# Power_Supplies.net
KiCad netlist of a schematic drawn in Altium Designer
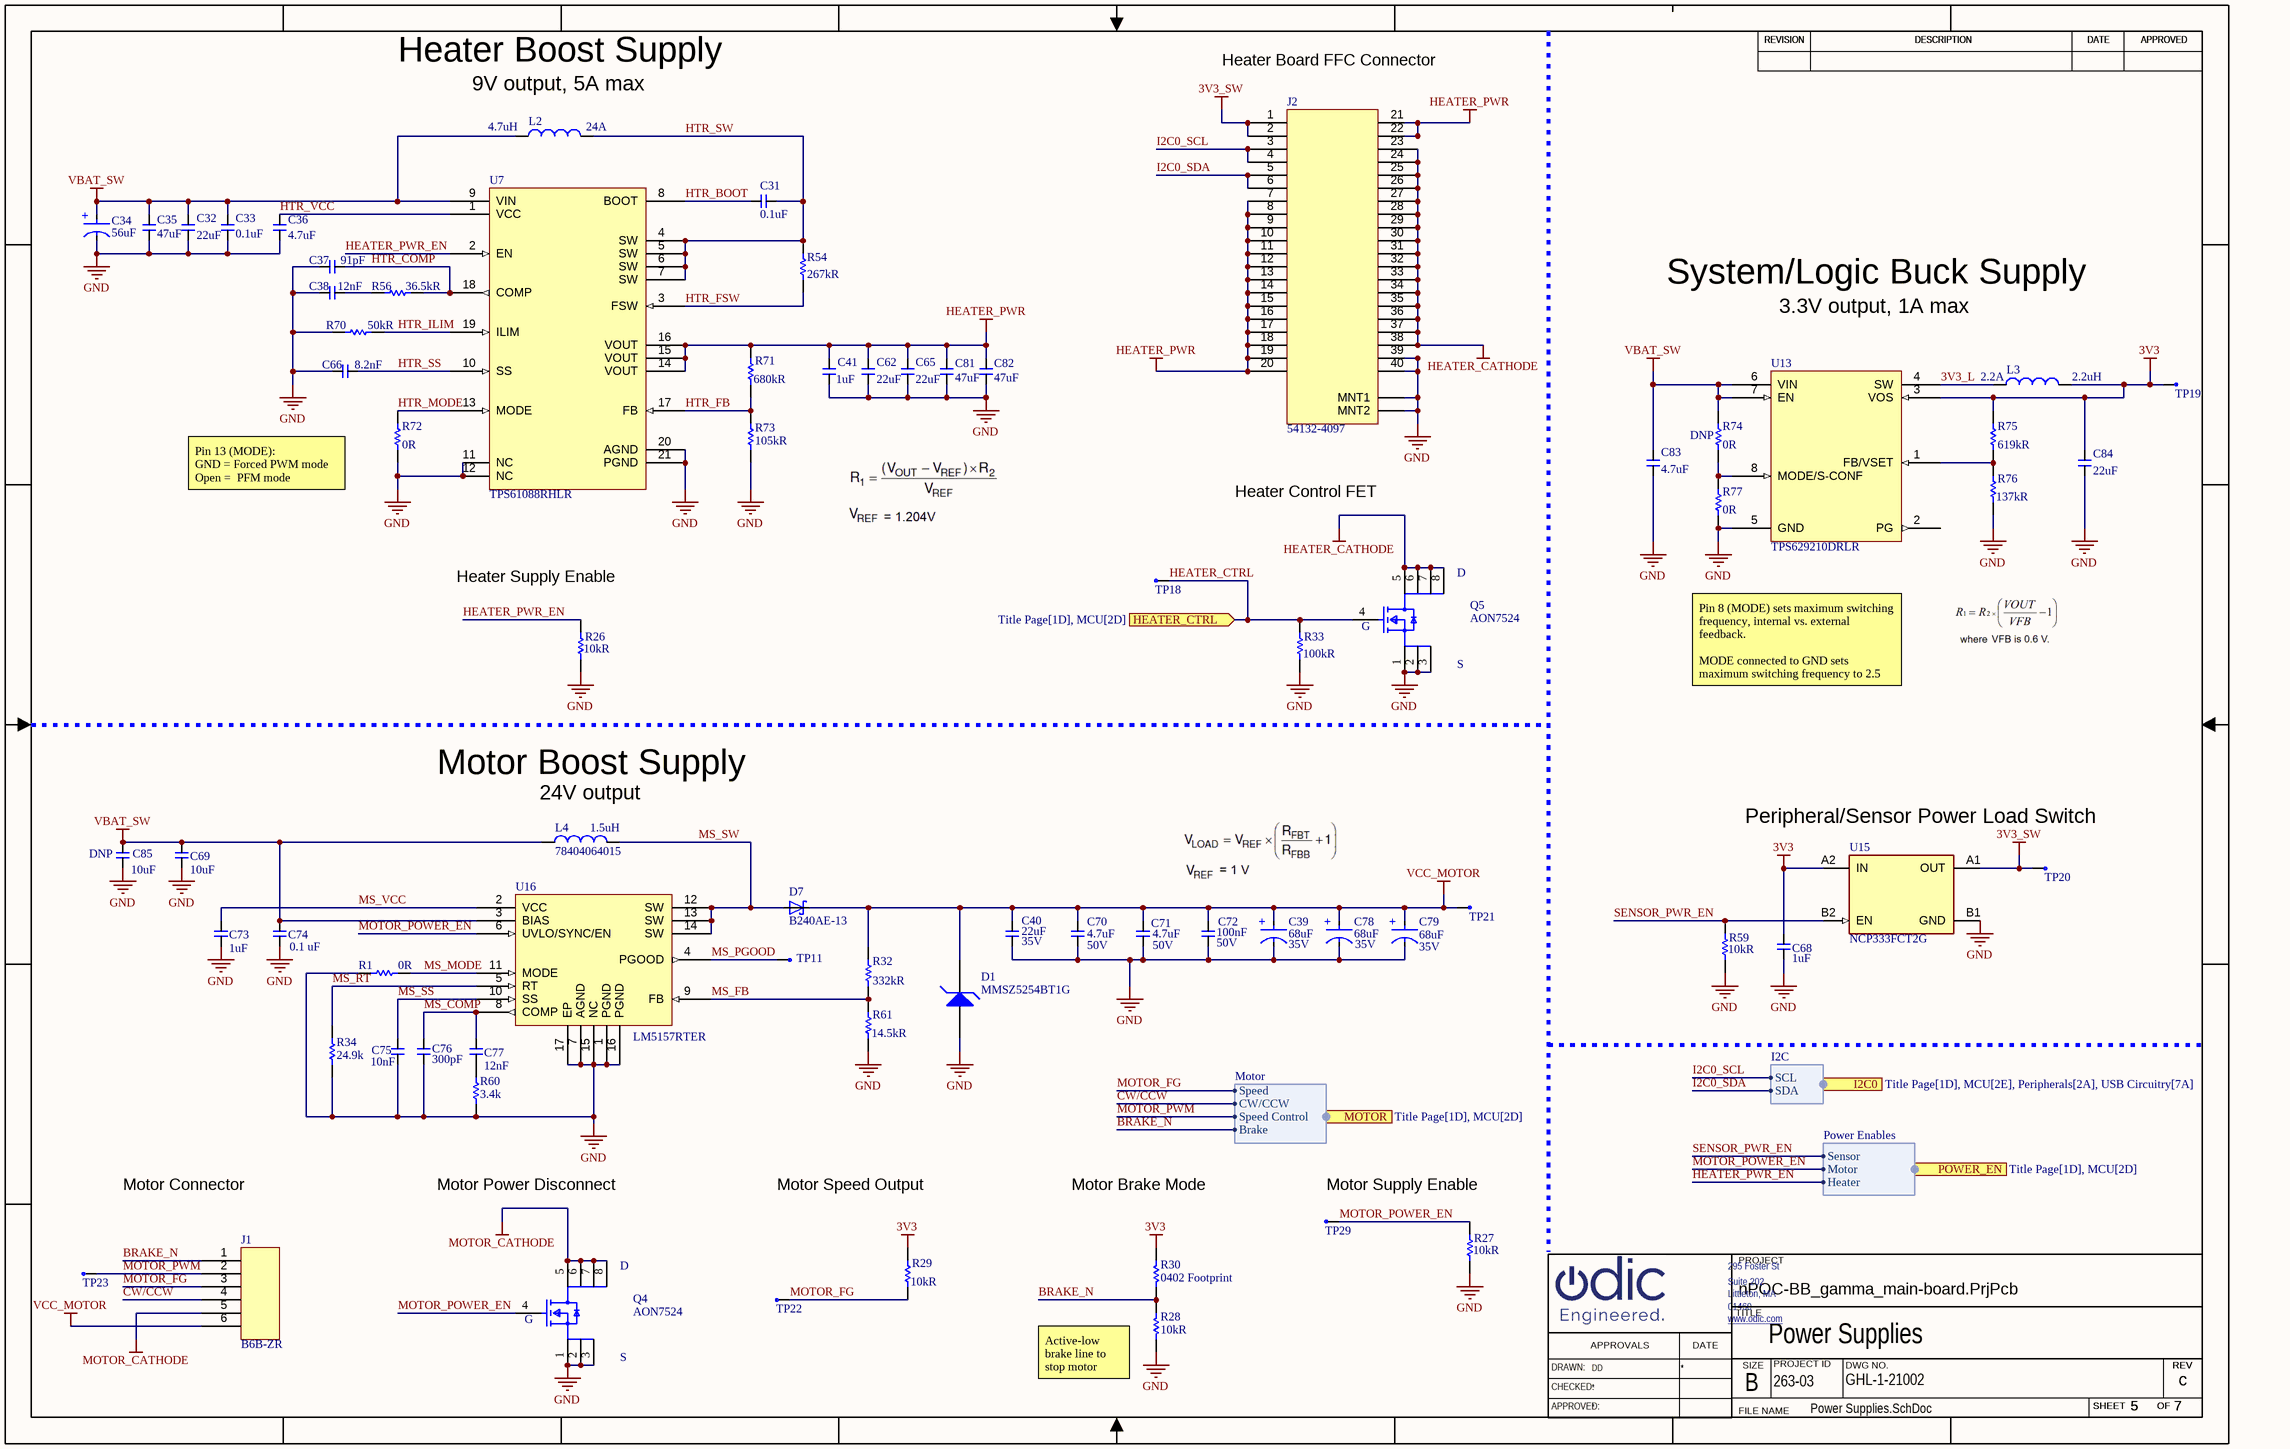
[diagram p0: Power Supplies.SchDoc]

(export (version "E")
  (design (tool "Eeschema 10.0.6"))
  (components
    (comp (ref "C31")
      (value "0.1uF")
      (footprint "C0402")
      (description "Ceramic capacitor SMD 0402 100nF 16V X7R 10%")
      (fields (field (name "VOLTAGE") "16V") (field (name "TOLERANCE") "10%"))
      (libsource (lib "Odic Inc") (part "cAP"))
    )
    (comp (ref "C32")
      (value "22uF")
      (footprint "C1206")
      (description "1206 22 uF 16 V ±10% Tolerance X5R SMT Multilayer Ceramic Capacitor")
      (fields (field (name "VOLTAGE") "16V") (field (name "TOLERANCE") "10%"))
      (libsource (lib "Odic Inc") (part "cAP"))
    )
    (comp (ref "C33")
      (value "0.1uF")
      (footprint "C0402")
      (description "Ceramic capacitor SMD 0402 100nF 16V X7R 10%")
      (fields (field (name "VOLTAGE") "16V") (field (name "TOLERANCE") "10%"))
      (libsource (lib "Odic Inc") (part "cAP"))
    )
    (comp (ref "C34")
      (value "56uF")
      (footprint "cap_panasonic_svpf_code-b6")
      (description "Cap Aluminum Polymer 56uF 20VDC 20%( 5 X 5.9mm) SMD 0.03 Ohm 2800mA 5000h 105C T/R")
      (fields (field (name "VOLTAGE") "20V") (field (name "TOLERANCE") "20%"))
      (libsource (lib "Odic Inc") (part "polcap"))
    )
    (comp (ref "C35")
      (value "47uF")
      (footprint "C1210")
      (description "Multilayer Ceramic Capacitor, 47 uF, 16 V, 10%, X5R, 1210 [3225 Metric]")
      (fields (field (name "TOLERANCE") "10%") (field (name "Comment") "C1210_47u_16V_10pct"))
      (libsource (lib "Odic Inc") (part "cAP"))
    )
    (comp (ref "C36")
      (value "4.7uF")
      (footprint "C0402")
      (description "Cap Ceramic 4.7uF 10V X5R 20% SMD 0402 85°C Paper T/R")
      (fields (field (name "TOLERANCE") "20%"))
      (libsource (lib "Odic Inc") (part "cAP"))
    )
    (comp (ref "C37")
      (value "91pF")
      (footprint "C0402")
      (description "Multilayer Ceramic Capacitors MLCC - SMD/SMT 50V 91pF C0G 0402 5%")
      (fields (field (name "TOLERANCE") "5%") (field (name "Comment") "C0402_91p_50V_5pct"))
      (libsource (lib "Odic Inc") (part "cAP"))
    )
    (comp (ref "C38")
      (value "12nF")
      (footprint "C0402")
      (description "0402 12 nF 16 V ±10% Tolerance X7R SMT Multilayer Ceramic Capacitor")
      (fields (field (name "VOLTAGE") "16V") (field (name "TOLERANCE") "10%"))
      (libsource (lib "Odic Inc") (part "cAP"))
    )
    (comp (ref "C39")
      (value "68uF")
      (footprint "C7361-38")
      (description "Cap Tant Solid 68uF 35V V CASE 20% (7.3 X 6.1 X 3.45mm) SMD 7361-38 0.5 Ohm 125AHA T/R")
      (fields
        (field (name "VOLTAGE RATING") "35V")
        (field (name "TOLERANCE") "20%")
        (field (name "Comment") "TAJV686M035RNJ")
      )
      (libsource (lib "Odic Inc") (part "polcap"))
    )
    (comp (ref "C40")
      (value "22uF")
      (footprint "c0805")
      (description "Multilayer Ceramic Capacitor, 22 uF, 35 V, ± 20%, X5R, 0805 [2012 Metric]")
      (fields
        (field (name "VOLTAGE RATING") "35V")
        (field (name "TOLERANCE") "20%")
        (field (name "Comment") "C0805_22u_35V_20pct")
      )
      (libsource (lib "Odic Inc") (part "cAP"))
    )
    (comp (ref "C41")
      (value "C0603_1u_25V_10pct")
      (footprint "C0603")
      (description "Multilayer Ceramic Capacitors (High dielectric type), 25V, 1 uF, ± 10 %, 0603, X5R/B, RoHS")
      (fields
        (field (name "CAPACITANCE") "1uF")
        (field (name "TOLERANCE") "10%")
        (field (name "VOLTAGE") "25V")
      )
      (libsource (lib "Odic Inc") (part "cAP"))
    )
    (comp (ref "C62")
      (value "22uF")
      (footprint "C1206")
      (description "1206 22 uF 16 V ±10% Tolerance X5R SMT Multilayer Ceramic Capacitor")
      (fields (field (name "VOLTAGE") "16V") (field (name "TOLERANCE") "10%"))
      (libsource (lib "Odic Inc") (part "cAP"))
    )
    (comp (ref "C65")
      (value "22uF")
      (footprint "C1206")
      (description "1206 22 uF 16 V ±10% Tolerance X5R SMT Multilayer Ceramic Capacitor")
      (fields (field (name "VOLTAGE") "16V") (field (name "TOLERANCE") "10%"))
      (libsource (lib "Odic Inc") (part "cAP"))
    )
    (comp (ref "C66")
      (value "8.2nF")
      (footprint "C0402")
      (description "0402 8.2 nF 16 V ±10% Tolerance X7R SMT Multilayer Ceramic Capacitor")
      (fields (field (name "TOLERANCE") "10%") (field (name "Comment") "C0402_8n2_16V_10pct"))
      (libsource (lib "Odic Inc") (part "cAP"))
    )
    (comp (ref "C68")
      (value "C0402_1u_6V3_10pct")
      (footprint "C0402")
      (description "Cap Ceramic 1uF 6.3V X5R 10% SMD 0402 85C Paper T/R")
      (fields (field (name "CAPACITANCE") "1uF") (field (name "TOLERANCE") "10%"))
      (libsource (lib "Odic Inc") (part "cAP"))
    )
    (comp (ref "C69")
      (value "10uF")
      (footprint "C0603")
      (description "Cap Ceramic 10uF 35V X5R 20% Pad SMD 0603 85C T/R")
      (fields (field (name "TOLERANCE") "20%"))
      (libsource (lib "Odic Inc") (part "cAP"))
    )
    (comp (ref "C70")
      (value "4.7uF")
      (footprint "c0805")
      (description "Multilayer Ceramic Capacitor, 4.7 uF, 50 V, ± 10%, X5R, 0805 [2012 Metric]")
      (fields
        (field (name "VOLTAGE RATING") "50V")
        (field (name "TOLERANCE") "10%")
        (field (name "Comment") "C0805_4u7_50V_10pct")
      )
      (libsource (lib "Odic Inc") (part "cAP"))
    )
    (comp (ref "C71")
      (value "4.7uF")
      (footprint "c0805")
      (description "Multilayer Ceramic Capacitor, 4.7 uF, 50 V, ± 10%, X5R, 0805 [2012 Metric]")
      (fields
        (field (name "VOLTAGE RATING") "50V")
        (field (name "TOLERANCE") "10%")
        (field (name "Comment") "C0805_4u7_50V_10pct")
      )
      (libsource (lib "Odic Inc") (part "cAP"))
    )
    (comp (ref "C72")
      (value "100nF")
      (footprint "C0603")
      (description "CAP CER 0.1UF 50V X7R 0603")
      (fields (field (name "VOLTAGE RATING") "50V") (field (name "TOLERANCE") "10%"))
      (libsource (lib "Odic Inc") (part "cAP"))
    )
    (comp (ref "C73")
      (value "1uF")
      (footprint "C0603")
      (description "CAP CER 1UF 16V X5R 0603")
      (fields (field (name "TOLERANCE") "10%") (field (name "VOLTAGE") "16V"))
      (libsource (lib "Odic Inc") (part "cAP"))
    )
    (comp (ref "C74")
      (value "C0805_0u1_25V_10pct")
      (footprint "c0805")
      (description "Cap Cer 0.1UF 25V X7R 0805")
      (fields (field (name "CAPACITANCE") "0.1 uF") (field (name "TOLERANCE") "10%"))
      (libsource (lib "Odic Inc") (part "cAP"))
    )
    (comp (ref "C75")
      (value "10nF")
      (footprint "C0402")
      (description "Multilayer Ceramic Capacitor, 0.01 uF, 35 V, ± 10%, X7R, 0402 [1005 Metric]")
      (fields (field (name "TOLERANCE") "10%") (field (name "Comment") "C0402_10n_35V_10pct"))
      (libsource (lib "Odic Inc") (part "cAP"))
    )
    (comp (ref "C76")
      (value "300pF")
      (footprint "C0402")
      (description "Cap Ceramic 300pF 50V C0G 5% SMD 0402 125°C Paper T/R")
      (fields (field (name "TOLERANCE") "5%") (field (name "Comment") "C0402_300p_50V_5pct"))
      (libsource (lib "Odic Inc") (part "cAP"))
    )
    (comp (ref "C77")
      (value "12nF")
      (footprint "C0402")
      (description "0402 12 nF 16 V ±10% Tolerance X7R SMT Multilayer Ceramic Capacitor")
      (fields (field (name "VOLTAGE") "16V") (field (name "TOLERANCE") "10%"))
      (libsource (lib "Odic Inc") (part "cAP"))
    )
    (comp (ref "C78")
      (value "68uF")
      (footprint "C7361-38")
      (description "Cap Tant Solid 68uF 35V V CASE 20% (7.3 X 6.1 X 3.45mm) SMD 7361-38 0.5 Ohm 125AHA T/R")
      (fields
        (field (name "VOLTAGE RATING") "35V")
        (field (name "TOLERANCE") "20%")
        (field (name "Comment") "TAJV686M035RNJ")
      )
      (libsource (lib "Odic Inc") (part "polcap"))
    )
    (comp (ref "C79")
      (value "68uF")
      (footprint "C7361-38")
      (description "Cap Tant Solid 68uF 35V V CASE 20% (7.3 X 6.1 X 3.45mm) SMD 7361-38 0.5 Ohm 125AHA T/R")
      (fields
        (field (name "VOLTAGE RATING") "35V")
        (field (name "TOLERANCE") "20%")
        (field (name "Comment") "TAJV686M035RNJ")
      )
      (libsource (lib "Odic Inc") (part "polcap"))
    )
    (comp (ref "C81")
      (value "47uF")
      (footprint "C1210")
      (description "Multilayer Ceramic Capacitor, 47 uF, 16 V, 10%, X5R, 1210 [3225 Metric]")
      (fields (field (name "TOLERANCE") "10%") (field (name "Comment") "C1210_47u_16V_10pct"))
      (libsource (lib "Odic Inc") (part "cAP"))
    )
    (comp (ref "C82")
      (value "47uF")
      (footprint "C1210")
      (description "Multilayer Ceramic Capacitor, 47 uF, 16 V, 10%, X5R, 1210 [3225 Metric]")
      (fields (field (name "TOLERANCE") "10%") (field (name "Comment") "C1210_47u_16V_10pct"))
      (libsource (lib "Odic Inc") (part "cAP"))
    )
    (comp (ref "C83")
      (value "4.7uF")
      (footprint "c0805")
      (description "Multilayer Ceramic Capacitor, 4.7 uF, 16 V, ± 10%, X5R, 0805 [2012 Metric]")
      (fields (field (name "VOLTAGE") "16V") (field (name "TOLERANCE") "10%"))
      (libsource (lib "Odic Inc") (part "cAP"))
    )
    (comp (ref "C84")
      (value "C0603_22u_6V3_20pct")
      (footprint "C0603")
      (description "CAP CER 22UF 6.3V X5R 0603")
      (fields
        (field (name "CAPACITANCE") "22uF")
        (field (name "TOLERANCE") "20%")
        (field (name "VOLTAGE") "6.3V")
      )
      (libsource (lib "Odic Inc") (part "cAP"))
    )
    (comp (ref "C85")
      (value "10uF")
      (footprint "C0603")
      (description "Cap Ceramic 10uF 35V X5R 20% Pad SMD 0603 85C T/R")
      (fields (field (name "INSTALL") "DNP") (field (name "TOLERANCE") "20%"))
      (libsource (lib "Odic Inc") (part "cAP"))
    )
    (comp (ref "D1")
      (value "MMSZ5254BT1G")
      (footprint "sod123")
      (description "MMSZ5254BT1G Zener Diode, 27V 5% 500 mW SMT 2-Pin SOD-123")
      (fields (field (name "TOLERANCE") "5%"))
      (libsource (lib "Odic Inc") (part "Zener Symbol"))
    )
    (comp (ref "D7")
      (value "B240AE-13")
      (footprint "sma")
      (description "Diode Schottky 40V 2A 2-Pin DO-214AC T/R")
      (libsource (lib "Odic Inc") (part "B240AE-13"))
    )
    (comp (ref "J1")
      (value "B6B-ZR")
      (footprint "jst-b6b-zr")
      (description "Header B6B-ZR, 1.50mm, 6-contacts, top entry, THT, /2000/box")
      (libsource (lib "Odic Inc") (part "B6B-ZR-Symbol-1"))
    )
    (comp (ref "J2")
      (value "54132-4097")
      (footprint "molex_54132-4097")
      (description ".50MM Ffc/fpc Connectors 40CKT R/a SMT Zif Botton Contact")
      (libsource (lib "Odic Inc") (part "54132-4097-Symbol-1"))
    )
    (comp (ref "L2")
      (value "4.7uH")
      (footprint "ind2_vishay_ihlp5050ce")
      (description "Inductor Power Shielded Wirewound 4.7uH 20% 100KHz Powdered Iron 10A 15mOhm DCR 5050 T/R")
      (fields
        (field (name "SATURATION CURRENT") "24A")
        (field (name "TOLERANCE") "20%")
        (field (name "Comment") "IHLP5050CEER4R7M01")
      )
      (libsource (lib "Odic Inc") (part "IND"))
    )
    (comp (ref "L3")
      (value "DFE252012PD-2R2M=P2")
      (footprint "ind2_2520")
      (description "Ind Power Chip Shielded Wirewound 2.2uH 20% 1MHz Metal 2.2A 1008 Emboss T/R")
      (fields
        (field (name "INDUCTANCE") "2.2uH")
        (field (name "CURRENT RATING") "2.2A")
        (field (name "TOLERANCE") "+/-20%")
      )
      (libsource (lib "Odic Inc") (part "IND"))
    )
    (comp (ref "L4")
      (value "78404064015")
      (footprint "ind2_wurth_78404064015")
      (description "WE-LQSA SMT Semi-Shielded Power Inductor 1.5uH 6.1 A 13mOhm Max")
      (fields (field (name "ALTIUM_VALUE") "1.5uH"))
      (libsource (lib "Odic Inc") (part "IND"))
    )
    (comp (ref "Q4")
      (value "AON7524")
      (footprint "dfn8_3x3_p65mm_fet")
      (description "Trans Mosfet N-ch 30V 28A 8-PIN Dfn-a Ep")
      (libsource (lib "Odic Inc") (part "e0baf4780622716b99a4fe4ad34e686"))
    )
    (comp (ref "Q5")
      (value "AON7524")
      (footprint "dfn8_3x3_p65mm_fet")
      (description "Trans Mosfet N-ch 30V 28A 8-PIN Dfn-a Ep")
      (libsource (lib "Odic Inc") (part "e0baf4780622716b99a4fe4ad34e686"))
    )
    (comp (ref "R1")
      (value "0R")
      (footprint "R0402")
      (description "RES 0 OHM JUMPER 1/16W 0402")
      (libsource (lib "Odic Inc") (part "RES"))
    )
    (comp (ref "R26")
      (value "R0402_10k_1pct")
      (footprint "R0402")
      (description "Res Thick Film 0402 10K Ohm 1% 1/16W ±100ppm/°C Molded SMD SMD T/R")
      (fields (field (name "RESISTANCE") "10kR") (field (name "TOLERANCE") "1%"))
      (libsource (lib "Odic Inc") (part "RES"))
    )
    (comp (ref "R27")
      (value "R0402_10k_1pct")
      (footprint "R0402")
      (description "Res Thick Film 0402 10K Ohm 1% 1/16W ±100ppm/°C Molded SMD SMD T/R")
      (fields (field (name "RESISTANCE") "10kR") (field (name "TOLERANCE") "1%"))
      (libsource (lib "Odic Inc") (part "RES"))
    )
    (comp (ref "R28")
      (value "R0402_10k_1pct")
      (footprint "R0402")
      (description "Res Thick Film 0402 10K Ohm 1% 1/16W ±100ppm/°C Molded SMD SMD T/R")
      (fields (field (name "RESISTANCE") "10kR") (field (name "TOLERANCE") "1%"))
      (libsource (lib "Odic Inc") (part "RES"))
    )
    (comp (ref "R29")
      (value "R0402_10k_1pct")
      (footprint "R0402")
      (description "Res Thick Film 0402 10K Ohm 1% 1/16W ±100ppm/°C Molded SMD SMD T/R")
      (fields (field (name "RESISTANCE") "10kR") (field (name "TOLERANCE") "1%"))
      (libsource (lib "Odic Inc") (part "RES"))
    )
    (comp (ref "R30")
      (value "0402 Footprint")
      (footprint "R0402")
      (description "Unpopulated 0402 pads. No part number associated with this \"component\"")
      (libsource (lib "Odic Inc") (part "RES"))
    )
    (comp (ref "R32")
      (value "332kR")
      (footprint "R0402")
      (description "Res Thick Film 0402 332K Ohm 1% 0.1W(1/10W) ±100ppm/°C Pad SMD Automotive T/R")
      (fields (field (name "TOLERANCE") "1%") (field (name "Comment") "R0402_332k_1pct"))
      (libsource (lib "Odic Inc") (part "RES"))
    )
    (comp (ref "R33")
      (value "R0402_100k_1pct")
      (footprint "R0402")
      (description "Res General Purpose Thick Film 0402 100K Ohm 1% 1/16W ±100ppm/°C Molded SMD Paper T/R")
      (fields (field (name "RESISTANCE") "100kR") (field (name "TOLERANCE") "1%"))
      (libsource (lib "Odic Inc") (part "RES"))
    )
    (comp (ref "R34")
      (value "24.9k")
      (footprint "R0402")
      (description "Res Thick Film 0402 24.9K Ohm 1% 1/10W ±100ppm/¦C SMD Punched Carrier T/R")
      (fields (field (name "TOLERANCE") "1%"))
      (libsource (lib "Odic Inc") (part "RES"))
    )
    (comp (ref "R54")
      (value "267kR")
      (footprint "R0402")
      (description "Res Thick Film 0402 267K Ohm 1% 0.063W ±100ppm/°C Molded SMD Paper T/R")
      (fields (field (name "TOLERANCE") "1%") (field (name "Comment") "R0402_267k_1pct"))
      (libsource (lib "Odic Inc") (part "RES"))
    )
    (comp (ref "R56")
      (value "36.5kR")
      (footprint "R0402")
      (description "SMD Chip Resistor, 36.5 kOhm, ï¿½ 1%, 63 mW, 0402 [1005 Metric], Thick Film, General Purpose")
      (fields (field (name "TOLERANCE") "1%") (field (name "Comment") "R0402_36k5_1pct"))
      (libsource (lib "Odic Inc") (part "RES"))
    )
    (comp (ref "R59")
      (value "R0402_10k_1pct")
      (footprint "R0402")
      (description "Res Thick Film 0402 10K Ohm 1% 1/16W ±100ppm/°C Molded SMD SMD T/R")
      (fields (field (name "RESISTANCE") "10kR") (field (name "TOLERANCE") "1%"))
      (libsource (lib "Odic Inc") (part "RES"))
    )
    (comp (ref "R60")
      (value "3.4k")
      (footprint "R0402")
      (description "SMD Chip Resistor, 3.4 kOhm, ± 1%, 100 mW, 0402 [1005 Metric], Thick Film, Precision")
      (fields (field (name "TOLERANCE") "1%"))
      (libsource (lib "Odic Inc") (part "RES"))
    )
    (comp (ref "R61")
      (value "14.5kR")
      (footprint "R0402")
      (description "RN73H 0402 (1005Metric) Chip Resistor ±1% ±25ppm/C 14.5kOhm 0.063W 1/16W")
      (fields (field (name "TOLERANCE") "1%") (field (name "Comment") "R0402_14k5_1pct"))
      (libsource (lib "Odic Inc") (part "RES"))
    )
    (comp (ref "R70")
      (value "50kR")
      (footprint "R0402")
      (fields (field (name "TOLERANCE") "1%") (field (name "Comment") "R0402_50k_1pct"))
      (libsource (lib "Odic Inc") (part "RES"))
    )
    (comp (ref "R71")
      (value "680kR")
      (footprint "R0402")
      (description "Res Thick Film 0402 680K Ohm 1% 1/16W ±100ppm/°C Molded SMD SMD Paper T/R")
      (fields (field (name "TOLERANCE") "1%") (field (name "Comment") "R0402_680k_1pct"))
      (libsource (lib "Odic Inc") (part "RES"))
    )
    (comp (ref "R72")
      (value "R0402_0R")
      (footprint "R0402")
      (description "RES 0 OHM JUMPER 1/16W 0402")
      (fields (field (name "RESISTANCE") "0R"))
      (libsource (lib "Odic Inc") (part "RES"))
    )
    (comp (ref "R73")
      (value "105kR")
      (footprint "R0402")
      (description "SMD Chip Resistor, 105 kOhm, ± 1%, 63 mW, 0402 [1005 Metric], Thick Film, General Purpose")
      (fields (field (name "TOLERANCE") "1%") (field (name "Comment") "R0402_105k_1pct"))
      (libsource (lib "Odic Inc") (part "RES"))
    )
    (comp (ref "R74")
      (value "R0402_0R")
      (footprint "R0402")
      (description "RES 0 OHM JUMPER 1/16W 0402")
      (fields (field (name "INSTALL") "DNP") (field (name "RESISTANCE") "0R"))
      (libsource (lib "Odic Inc") (part "RES"))
    )
    (comp (ref "R75")
      (value "619kR")
      (footprint "R0402")
      (description "RC FIXED RESISTOR 0402 (1005Metric) Chip Resistor ±1% ±100ppm/C 619kOhm 0.063W 1/16W")
      (fields (field (name "TOLERANCE") "1%") (field (name "Comment") "R0402_619k_1pct"))
      (libsource (lib "Odic Inc") (part "RES"))
    )
    (comp (ref "R76")
      (value "137kR")
      (footprint "R0402")
      (description "SMD Chip Resistor, 137 kOhm, ± 1%, 63 mW, 0402 [1005 Metric], Thick Film, General Purpose")
      (fields (field (name "TOLERANCE") "1%") (field (name "Comment") "R0402_137k_1pct"))
      (libsource (lib "Odic Inc") (part "RES"))
    )
    (comp (ref "R77")
      (value "R0402_0R")
      (footprint "R0402")
      (description "RES 0 OHM JUMPER 1/16W 0402")
      (fields (field (name "RESISTANCE") "0R"))
      (libsource (lib "Odic Inc") (part "RES"))
    )
    (comp (ref "TP11")
      (value "TPC30")
      (footprint "tpc30")
      (description "Test Point Circle 30")
      (libsource (lib "Odic Inc") (part "TPC"))
    )
    (comp (ref "TP18")
      (value "TPC30")
      (footprint "tpc30")
      (description "Test Point Circle 30")
      (libsource (lib "Odic Inc") (part "TPC"))
    )
    (comp (ref "TP19")
      (value "TPC30")
      (footprint "tpc30")
      (description "Test Point Circle 30")
      (libsource (lib "Odic Inc") (part "TPC"))
    )
    (comp (ref "TP20")
      (value "TPC30")
      (footprint "tpc30")
      (description "Test Point Circle 30")
      (libsource (lib "Odic Inc") (part "TPC"))
    )
    (comp (ref "TP21")
      (value "TPC30")
      (footprint "tpc30")
      (description "Test Point Circle 30")
      (libsource (lib "Odic Inc") (part "TPC"))
    )
    (comp (ref "TP22")
      (value "TPC30")
      (footprint "tpc30")
      (description "Test Point Circle 30")
      (libsource (lib "Odic Inc") (part "TPC"))
    )
    (comp (ref "TP23")
      (value "TPC30")
      (footprint "tpc30")
      (description "Test Point Circle 30")
      (libsource (lib "Odic Inc") (part "TPC"))
    )
    (comp (ref "TP29")
      (value "TPC30")
      (footprint "tpc30")
      (description "Test Point Circle 30")
      (libsource (lib "Odic Inc") (part "TPC"))
    )
    (comp (ref "U7")
      (value "TPS61088RHLR")
      (footprint "qfn20_3p5x4p5_p5mm")
      (description "IC REG BOOST ADJ 10A SYNC 20VQFN")
      (libsource (lib "Odic Inc") (part "TPS61088RHLR-Symbol-1"))
    )
    (comp (ref "U13")
      (value "TPS629210DRLR")
      (footprint "SOT-583")
      (libsource (lib "Odic Inc") (part "TPS629210DRLR-Symbol-1"))
    )
    (comp (ref "U15")
      (value "NCP333FCT2G")
      (footprint "bga4_p743xp743_p4mm")
      (description "IC LOAD SWITCH W/DIS 1.5A 4WLCSP")
      (libsource (lib "Odic Inc") (part "97019fd276bc7644be76e1f711e9589"))
    )
    (comp (ref "U16")
      (value "LM5157RTER")
      (footprint "qfn16_3x3_p5mm_thpad")
      (libsource (lib "Odic Inc") (part "LM5157RTER-Symbol-1"))
    )
  )
  (nets
    (net (code "5") (name "/3V3_L") (class "Default")
      (node (ref "L3") (pin "1") (pinfunction "1_1") (pintype "passive"))
      (node (ref "U13") (pin "4") (pinfunction "SW_4") (pintype "passive"))
    )
    (net (code "6") (name "/BRAKE_N") (class "Default")
      (node (ref "J1") (pin "1") (pinfunction "1_1") (pintype "passive"))
      (node (ref "R28") (pin "1") (pinfunction "1_1") (pintype "passive"))
      (node (ref "R30") (pin "2") (pinfunction "2_2") (pintype "passive"))
    )
    (net (code "7") (name "/CW{slash}CCW") (class "Default")
      (node (ref "J1") (pin "4") (pinfunction "4_4") (pintype "passive"))
    )
    (net (code "8") (name "/HEATER_CTRL") (class "Default")
      (node (ref "Q5") (pin "4") (pinfunction "G_4") (pintype "passive"))
      (node (ref "R33") (pin "2") (pinfunction "2_2") (pintype "passive"))
      (node (ref "TP18") (pin "1") (pinfunction "1_1") (pintype "passive"))
    )
    (net (code "9") (name "/HEATER_PWR_EN") (class "Default")
      (node (ref "R26") (pin "1") (pinfunction "1_1") (pintype "passive"))
      (node (ref "U7") (pin "2") (pinfunction "EN_2") (pintype "input"))
    )
    (net (code "10") (name "/HTR_BOOT") (class "Default")
      (node (ref "C31") (pin "2") (pinfunction "2_2") (pintype "passive"))
      (node (ref "U7") (pin "8") (pinfunction "BOOT_8") (pintype "passive"))
    )
    (net (code "11") (name "/HTR_COMP") (class "Default")
      (node (ref "C37") (pin "2") (pinfunction "2_2") (pintype "passive"))
      (node (ref "R56") (pin "2") (pinfunction "2_2") (pintype "passive"))
      (node (ref "U7") (pin "18") (pinfunction "COMP_18") (pintype "output"))
    )
    (net (code "12") (name "/HTR_FB") (class "Default")
      (node (ref "R71") (pin "1") (pinfunction "1_1") (pintype "passive"))
      (node (ref "R73") (pin "2") (pinfunction "2_2") (pintype "passive"))
      (node (ref "U7") (pin "17") (pinfunction "FB_17") (pintype "input"))
    )
    (net (code "13") (name "/HTR_FSW") (class "Default")
      (node (ref "R54") (pin "1") (pinfunction "1_1") (pintype "passive"))
      (node (ref "U7") (pin "3") (pinfunction "FSW_3") (pintype "input"))
    )
    (net (code "14") (name "/HTR_ILIM") (class "Default")
      (node (ref "R70") (pin "2") (pinfunction "2_2") (pintype "passive"))
      (node (ref "U7") (pin "19") (pinfunction "ILIM_19") (pintype "input"))
    )
    (net (code "15") (name "/HTR_MODE") (class "Default")
      (node (ref "R72") (pin "2") (pinfunction "2_2") (pintype "passive"))
      (node (ref "U7") (pin "13") (pinfunction "MODE_13") (pintype "input"))
    )
    (net (code "16") (name "/HTR_SS") (class "Default")
      (node (ref "C66") (pin "2") (pinfunction "2_2") (pintype "passive"))
      (node (ref "U7") (pin "10") (pinfunction "SS_10") (pintype "input"))
    )
    (net (code "17") (name "/HTR_SW") (class "Default")
      (node (ref "C31") (pin "1") (pinfunction "1_1") (pintype "passive"))
      (node (ref "L2") (pin "2") (pinfunction "2_2") (pintype "passive"))
      (node (ref "R54") (pin "2") (pinfunction "2_2") (pintype "passive"))
      (node (ref "U7") (pin "4") (pinfunction "SW_4") (pintype "passive"))
      (node (ref "U7") (pin "5") (pinfunction "SW_5") (pintype "passive"))
      (node (ref "U7") (pin "6") (pinfunction "SW_6") (pintype "passive"))
      (node (ref "U7") (pin "7") (pinfunction "SW_7") (pintype "passive"))
    )
    (net (code "18") (name "/HTR_VCC") (class "Default")
      (node (ref "C36") (pin "2") (pinfunction "2_2") (pintype "passive"))
      (node (ref "U7") (pin "1") (pinfunction "VCC_1") (pintype "passive"))
    )
    (net (code "19") (name "/I2C0_SCL") (class "Default")
      (node (ref "J2") (pin "3") (pinfunction "3_3") (pintype "passive"))
      (node (ref "J2") (pin "4") (pinfunction "4_4") (pintype "passive"))
    )
    (net (code "20") (name "/I2C0_SDA") (class "Default")
      (node (ref "J2") (pin "5") (pinfunction "5_5") (pintype "passive"))
      (node (ref "J2") (pin "6") (pinfunction "6_6") (pintype "passive"))
    )
    (net (code "21") (name "/MOTOR_FG") (class "Default")
      (node (ref "J1") (pin "3") (pinfunction "3_3") (pintype "passive"))
      (node (ref "R29") (pin "1") (pinfunction "1_1") (pintype "passive"))
      (node (ref "TP22") (pin "1") (pinfunction "1_1") (pintype "passive"))
    )
    (net (code "22") (name "/MOTOR_POWER_EN") (class "Default")
      (node (ref "Q4") (pin "4") (pinfunction "G_4") (pintype "passive"))
      (node (ref "R27") (pin "1") (pinfunction "1_1") (pintype "passive"))
      (node (ref "TP29") (pin "1") (pinfunction "1_1") (pintype "passive"))
      (node (ref "U16") (pin "6") (pinfunction "UVLO/SYNC/EN_6") (pintype "input"))
    )
    (net (code "23") (name "/MOTOR_PWM") (class "Default")
      (node (ref "J1") (pin "2") (pinfunction "2_2") (pintype "passive"))
      (node (ref "TP23") (pin "1") (pinfunction "1_1") (pintype "passive"))
    )
    (net (code "24") (name "/MS_COMP") (class "Default")
      (node (ref "C76") (pin "2") (pinfunction "2_2") (pintype "passive"))
      (node (ref "C77") (pin "2") (pinfunction "2_2") (pintype "passive"))
      (node (ref "U16") (pin "8") (pinfunction "COMP_8") (pintype "output"))
    )
    (net (code "25") (name "/MS_FB") (class "Default")
      (node (ref "R32") (pin "1") (pinfunction "1_1") (pintype "passive"))
      (node (ref "R61") (pin "2") (pinfunction "2_2") (pintype "passive"))
      (node (ref "U16") (pin "9") (pinfunction "FB_9") (pintype "input"))
    )
    (net (code "26") (name "/MS_MODE") (class "Default")
      (node (ref "R1") (pin "2") (pinfunction "2_2") (pintype "passive"))
      (node (ref "U16") (pin "11") (pinfunction "MODE_11") (pintype "input"))
    )
    (net (code "27") (name "/MS_PGOOD") (class "Default")
      (node (ref "TP11") (pin "1") (pinfunction "1_1") (pintype "passive"))
      (node (ref "U16") (pin "4") (pinfunction "PGOOD_4") (pintype "output"))
    )
    (net (code "28") (name "/MS_RT") (class "Default")
      (node (ref "R34") (pin "2") (pinfunction "2_2") (pintype "passive"))
      (node (ref "U16") (pin "5") (pinfunction "RT_5") (pintype "input"))
    )
    (net (code "29") (name "/MS_SS") (class "Default")
      (node (ref "C75") (pin "2") (pinfunction "2_2") (pintype "passive"))
      (node (ref "U16") (pin "10") (pinfunction "SS_10") (pintype "input"))
    )
    (net (code "30") (name "/MS_SW") (class "Default")
      (node (ref "D7") (pin "A") (pinfunction "A_A") (pintype "passive"))
      (node (ref "L4") (pin "2") (pinfunction "2_2") (pintype "passive"))
      (node (ref "U16") (pin "12") (pinfunction "SW_12") (pintype "passive"))
      (node (ref "U16") (pin "13") (pinfunction "SW_13") (pintype "passive"))
      (node (ref "U16") (pin "14") (pinfunction "SW_14") (pintype "passive"))
    )
    (net (code "31") (name "/MS_VCC") (class "Default")
      (node (ref "C73") (pin "2") (pinfunction "2_2") (pintype "passive"))
      (node (ref "U16") (pin "2") (pinfunction "VCC_2") (pintype "power_in"))
    )
    (net (code "32") (name "/SENSOR_PWR_EN") (class "Default")
      (node (ref "R59") (pin "1") (pinfunction "1_1") (pintype "passive"))
      (node (ref "U15") (pin "B2") (pinfunction "EN_B2") (pintype "input"))
    )
    (net (code "36") (name "3V3") (class "Default")
      (node (ref "C68") (pin "2") (pinfunction "2_2") (pintype "passive"))
      (node (ref "C84") (pin "2") (pinfunction "2_2") (pintype "passive"))
      (node (ref "L3") (pin "2") (pinfunction "2_2") (pintype "passive"))
      (node (ref "R29") (pin "2") (pinfunction "2_2") (pintype "passive"))
      (node (ref "R30") (pin "1") (pinfunction "1_1") (pintype "passive"))
      (node (ref "R75") (pin "2") (pinfunction "2_2") (pintype "passive"))
      (node (ref "TP19") (pin "1") (pinfunction "1_1") (pintype "passive"))
      (node (ref "U13") (pin "3") (pinfunction "VOS_3") (pintype "input"))
      (node (ref "U15") (pin "A2") (pinfunction "IN_A2") (pintype "power_in"))
    )
    (net (code "37") (name "3V3_SW") (class "Default")
      (node (ref "J2") (pin "1") (pinfunction "1_1") (pintype "passive"))
      (node (ref "J2") (pin "2") (pinfunction "2_2") (pintype "passive"))
      (node (ref "TP20") (pin "1") (pinfunction "1_1") (pintype "passive"))
      (node (ref "U15") (pin "A1") (pinfunction "OUT_A1") (pintype "power_in"))
    )
    (net (code "38") (name "GND") (class "Default")
      (node (ref "C32") (pin "1") (pinfunction "1_1") (pintype "passive"))
      (node (ref "C33") (pin "2") (pinfunction "2_2") (pintype "passive"))
      (node (ref "C34") (pin "2") (pinfunction "2_2") (pintype "passive"))
      (node (ref "C35") (pin "1") (pinfunction "1_1") (pintype "passive"))
      (node (ref "C36") (pin "1") (pinfunction "1_1") (pintype "passive"))
      (node (ref "C37") (pin "1") (pinfunction "1_1") (pintype "passive"))
      (node (ref "C38") (pin "1") (pinfunction "1_1") (pintype "passive"))
      (node (ref "C39") (pin "2") (pinfunction "2_2") (pintype "passive"))
      (node (ref "C40") (pin "1") (pinfunction "1_1") (pintype "passive"))
      (node (ref "C41") (pin "1") (pinfunction "1_1") (pintype "passive"))
      (node (ref "C62") (pin "1") (pinfunction "1_1") (pintype "passive"))
      (node (ref "C65") (pin "1") (pinfunction "1_1") (pintype "passive"))
      (node (ref "C66") (pin "1") (pinfunction "1_1") (pintype "passive"))
      (node (ref "C68") (pin "1") (pinfunction "1_1") (pintype "passive"))
      (node (ref "C69") (pin "1") (pinfunction "1_1") (pintype "passive"))
      (node (ref "C70") (pin "1") (pinfunction "1_1") (pintype "passive"))
      (node (ref "C71") (pin "1") (pinfunction "1_1") (pintype "passive"))
      (node (ref "C72") (pin "1") (pinfunction "1_1") (pintype "passive"))
      (node (ref "C73") (pin "1") (pinfunction "1_1") (pintype "passive"))
      (node (ref "C74") (pin "1") (pinfunction "1_1") (pintype "passive"))
      (node (ref "C75") (pin "1") (pinfunction "1_1") (pintype "passive"))
      (node (ref "C76") (pin "1") (pinfunction "1_1") (pintype "passive"))
      (node (ref "C78") (pin "2") (pinfunction "2_2") (pintype "passive"))
      (node (ref "C79") (pin "2") (pinfunction "2_2") (pintype "passive"))
      (node (ref "C81") (pin "1") (pinfunction "1_1") (pintype "passive"))
      (node (ref "C82") (pin "1") (pinfunction "1_1") (pintype "passive"))
      (node (ref "C83") (pin "1") (pinfunction "1_1") (pintype "passive"))
      (node (ref "C84") (pin "1") (pinfunction "1_1") (pintype "passive"))
      (node (ref "C85") (pin "1") (pinfunction "1_1") (pintype "passive"))
      (node (ref "D1") (pin "A") (pinfunction "A_A") (pintype "passive"))
      (node (ref "J2") (pin "39") (pinfunction "39_39") (pintype "passive"))
      (node (ref "J2") (pin "40") (pinfunction "40_40") (pintype "passive"))
      (node (ref "J2") (pin "MNT1") (pinfunction "MNT1_MNT1") (pintype "passive"))
      (node (ref "J2") (pin "MNT2") (pinfunction "MNT2_MNT2") (pintype "passive"))
      (node (ref "Q4") (pin "1") (pinfunction "S_1") (pintype "passive"))
      (node (ref "Q4") (pin "2") (pinfunction "S_2") (pintype "passive"))
      (node (ref "Q4") (pin "3") (pinfunction "S_3") (pintype "passive"))
      (node (ref "Q5") (pin "1") (pinfunction "S_1") (pintype "passive"))
      (node (ref "Q5") (pin "2") (pinfunction "S_2") (pintype "passive"))
      (node (ref "Q5") (pin "3") (pinfunction "S_3") (pintype "passive"))
      (node (ref "R1") (pin "1") (pinfunction "1_1") (pintype "passive"))
      (node (ref "R26") (pin "2") (pinfunction "2_2") (pintype "passive"))
      (node (ref "R27") (pin "2") (pinfunction "2_2") (pintype "passive"))
      (node (ref "R28") (pin "2") (pinfunction "2_2") (pintype "passive"))
      (node (ref "R33") (pin "1") (pinfunction "1_1") (pintype "passive"))
      (node (ref "R34") (pin "1") (pinfunction "1_1") (pintype "passive"))
      (node (ref "R59") (pin "2") (pinfunction "2_2") (pintype "passive"))
      (node (ref "R60") (pin "1") (pinfunction "1_1") (pintype "passive"))
      (node (ref "R61") (pin "1") (pinfunction "1_1") (pintype "passive"))
      (node (ref "R70") (pin "1") (pinfunction "1_1") (pintype "passive"))
      (node (ref "R72") (pin "1") (pinfunction "1_1") (pintype "passive"))
      (node (ref "R73") (pin "1") (pinfunction "1_1") (pintype "passive"))
      (node (ref "R76") (pin "1") (pinfunction "1_1") (pintype "passive"))
      (node (ref "R77") (pin "1") (pinfunction "1_1") (pintype "passive"))
      (node (ref "U13") (pin "5") (pinfunction "GND_5") (pintype "passive"))
      (node (ref "U15") (pin "B1") (pinfunction "GND_B1") (pintype "power_in"))
      (node (ref "U16") (pin "1") (pinfunction "PGND_1") (pintype "passive"))
      (node (ref "U16") (pin "15") (pinfunction "NC_15") (pintype "passive"))
      (node (ref "U16") (pin "16") (pinfunction "PGND_16") (pintype "passive"))
      (node (ref "U16") (pin "17") (pinfunction "EP_17") (pintype "passive"))
      (node (ref "U16") (pin "7") (pinfunction "AGND_7") (pintype "passive"))
      (node (ref "U7") (pin "11") (pinfunction "NC_11") (pintype "passive"))
      (node (ref "U7") (pin "12") (pinfunction "NC_12") (pintype "passive"))
      (node (ref "U7") (pin "20") (pinfunction "AGND_20") (pintype "passive"))
      (node (ref "U7") (pin "21") (pinfunction "PGND_21") (pintype "passive"))
    )
    (net (code "39") (name "HEATER_CATHODE") (class "Default")
      (node (ref "J2") (pin "23") (pinfunction "23_23") (pintype "passive"))
      (node (ref "J2") (pin "24") (pinfunction "24_24") (pintype "passive"))
      (node (ref "J2") (pin "25") (pinfunction "25_25") (pintype "passive"))
      (node (ref "J2") (pin "26") (pinfunction "26_26") (pintype "passive"))
      (node (ref "J2") (pin "27") (pinfunction "27_27") (pintype "passive"))
      (node (ref "J2") (pin "28") (pinfunction "28_28") (pintype "passive"))
      (node (ref "J2") (pin "29") (pinfunction "29_29") (pintype "passive"))
      (node (ref "J2") (pin "30") (pinfunction "30_30") (pintype "passive"))
      (node (ref "J2") (pin "31") (pinfunction "31_31") (pintype "passive"))
      (node (ref "J2") (pin "32") (pinfunction "32_32") (pintype "passive"))
      (node (ref "J2") (pin "33") (pinfunction "33_33") (pintype "passive"))
      (node (ref "J2") (pin "34") (pinfunction "34_34") (pintype "passive"))
      (node (ref "J2") (pin "35") (pinfunction "35_35") (pintype "passive"))
      (node (ref "J2") (pin "36") (pinfunction "36_36") (pintype "passive"))
      (node (ref "J2") (pin "37") (pinfunction "37_37") (pintype "passive"))
      (node (ref "J2") (pin "38") (pinfunction "38_38") (pintype "passive"))
      (node (ref "Q5") (pin "5") (pinfunction "D_5") (pintype "passive"))
      (node (ref "Q5") (pin "6") (pinfunction "D_6") (pintype "passive"))
      (node (ref "Q5") (pin "7") (pinfunction "D_7") (pintype "passive"))
      (node (ref "Q5") (pin "8") (pinfunction "D_8") (pintype "passive"))
    )
    (net (code "40") (name "HEATER_PWR") (class "Default")
      (node (ref "C41") (pin "2") (pinfunction "2_2") (pintype "passive"))
      (node (ref "C62") (pin "2") (pinfunction "2_2") (pintype "passive"))
      (node (ref "C65") (pin "2") (pinfunction "2_2") (pintype "passive"))
      (node (ref "C81") (pin "2") (pinfunction "2_2") (pintype "passive"))
      (node (ref "C82") (pin "2") (pinfunction "2_2") (pintype "passive"))
      (node (ref "J2") (pin "10") (pinfunction "10_10") (pintype "passive"))
      (node (ref "J2") (pin "11") (pinfunction "11_11") (pintype "passive"))
      (node (ref "J2") (pin "12") (pinfunction "12_12") (pintype "passive"))
      (node (ref "J2") (pin "13") (pinfunction "13_13") (pintype "passive"))
      (node (ref "J2") (pin "14") (pinfunction "14_14") (pintype "passive"))
      (node (ref "J2") (pin "15") (pinfunction "15_15") (pintype "passive"))
      (node (ref "J2") (pin "16") (pinfunction "16_16") (pintype "passive"))
      (node (ref "J2") (pin "17") (pinfunction "17_17") (pintype "passive"))
      (node (ref "J2") (pin "18") (pinfunction "18_18") (pintype "passive"))
      (node (ref "J2") (pin "19") (pinfunction "19_19") (pintype "passive"))
      (node (ref "J2") (pin "20") (pinfunction "20_20") (pintype "passive"))
      (node (ref "J2") (pin "21") (pinfunction "21_21") (pintype "passive"))
      (node (ref "J2") (pin "22") (pinfunction "22_22") (pintype "passive"))
      (node (ref "J2") (pin "7") (pinfunction "7_7") (pintype "passive"))
      (node (ref "J2") (pin "8") (pinfunction "8_8") (pintype "passive"))
      (node (ref "J2") (pin "9") (pinfunction "9_9") (pintype "passive"))
      (node (ref "R71") (pin "2") (pinfunction "2_2") (pintype "passive"))
      (node (ref "U7") (pin "14") (pinfunction "VOUT_14") (pintype "power_in"))
      (node (ref "U7") (pin "15") (pinfunction "VOUT_15") (pintype "power_in"))
      (node (ref "U7") (pin "16") (pinfunction "VOUT_16") (pintype "power_in"))
    )
    (net (code "41") (name "MOTOR_CATHODE") (class "Default")
      (node (ref "J1") (pin "5") (pinfunction "5_5") (pintype "passive"))
      (node (ref "Q4") (pin "5") (pinfunction "D_5") (pintype "passive"))
      (node (ref "Q4") (pin "6") (pinfunction "D_6") (pintype "passive"))
      (node (ref "Q4") (pin "7") (pinfunction "D_7") (pintype "passive"))
      (node (ref "Q4") (pin "8") (pinfunction "D_8") (pintype "passive"))
    )
    (net (code "42") (name "Net-(C38-Pad2)") (class "Default")
      (node (ref "C38") (pin "2") (pinfunction "2_2") (pintype "passive"))
      (node (ref "R56") (pin "1") (pinfunction "1_1") (pintype "passive"))
    )
    (net (code "43") (name "Net-(C77-Pad1)") (class "Default")
      (node (ref "C77") (pin "1") (pinfunction "1_1") (pintype "passive"))
      (node (ref "R60") (pin "2") (pinfunction "2_2") (pintype "passive"))
    )
    (net (code "44") (name "Net-(U13-FB{slash}VSET)") (class "Default")
      (node (ref "R75") (pin "1") (pinfunction "1_1") (pintype "passive"))
      (node (ref "R76") (pin "2") (pinfunction "2_2") (pintype "passive"))
      (node (ref "U13") (pin "1") (pinfunction "FB/VSET_1") (pintype "input"))
    )
    (net (code "45") (name "Net-(U13-MODE{slash}S-CONF)") (class "Default")
      (node (ref "R74") (pin "1") (pinfunction "1_1") (pintype "passive"))
      (node (ref "R77") (pin "2") (pinfunction "2_2") (pintype "passive"))
      (node (ref "U13") (pin "8") (pinfunction "MODE/S-CONF_8") (pintype "input"))
    )
    (net (code "46") (name "VBAT_SW") (class "Default")
      (node (ref "C32") (pin "2") (pinfunction "2_2") (pintype "passive"))
      (node (ref "C33") (pin "1") (pinfunction "1_1") (pintype "passive"))
      (node (ref "C34") (pin "1") (pinfunction "1_1") (pintype "passive"))
      (node (ref "C35") (pin "2") (pinfunction "2_2") (pintype "passive"))
      (node (ref "C69") (pin "2") (pinfunction "2_2") (pintype "passive"))
      (node (ref "C74") (pin "2") (pinfunction "2_2") (pintype "passive"))
      (node (ref "C83") (pin "2") (pinfunction "2_2") (pintype "passive"))
      (node (ref "C85") (pin "2") (pinfunction "2_2") (pintype "passive"))
      (node (ref "L2") (pin "1") (pinfunction "1_1") (pintype "passive"))
      (node (ref "L4") (pin "1") (pinfunction "1_1") (pintype "passive"))
      (node (ref "R74") (pin "2") (pinfunction "2_2") (pintype "passive"))
      (node (ref "U13") (pin "6") (pinfunction "VIN_6") (pintype "power_in"))
      (node (ref "U13") (pin "7") (pinfunction "EN_7") (pintype "input"))
      (node (ref "U16") (pin "3") (pinfunction "BIAS_3") (pintype "power_in"))
      (node (ref "U7") (pin "9") (pinfunction "VIN_9") (pintype "passive"))
    )
    (net (code "47") (name "VCC_MOTOR") (class "Default")
      (node (ref "C39") (pin "1") (pinfunction "1_1") (pintype "passive"))
      (node (ref "C40") (pin "2") (pinfunction "2_2") (pintype "passive"))
      (node (ref "C70") (pin "2") (pinfunction "2_2") (pintype "passive"))
      (node (ref "C71") (pin "2") (pinfunction "2_2") (pintype "passive"))
      (node (ref "C72") (pin "2") (pinfunction "2_2") (pintype "passive"))
      (node (ref "C78") (pin "1") (pinfunction "1_1") (pintype "passive"))
      (node (ref "C79") (pin "1") (pinfunction "1_1") (pintype "passive"))
      (node (ref "D1") (pin "K") (pinfunction "K_K") (pintype "passive"))
      (node (ref "D7") (pin "K") (pinfunction "K_K") (pintype "passive"))
      (node (ref "J1") (pin "6") (pinfunction "6_6") (pintype "passive"))
      (node (ref "R32") (pin "2") (pinfunction "2_2") (pintype "passive"))
      (node (ref "TP21") (pin "1") (pinfunction "1_1") (pintype "passive"))
    )
    (net (code "48") (name "unconnected-(U13-PG-Pad2)") (class "Default")
      (node (ref "U13") (pin "2") (pinfunction "PG_2") (pintype "output"))
    )
  )
)
